# ssb-shield.net
KiCad netlist of a schematic drawn in EAGLE
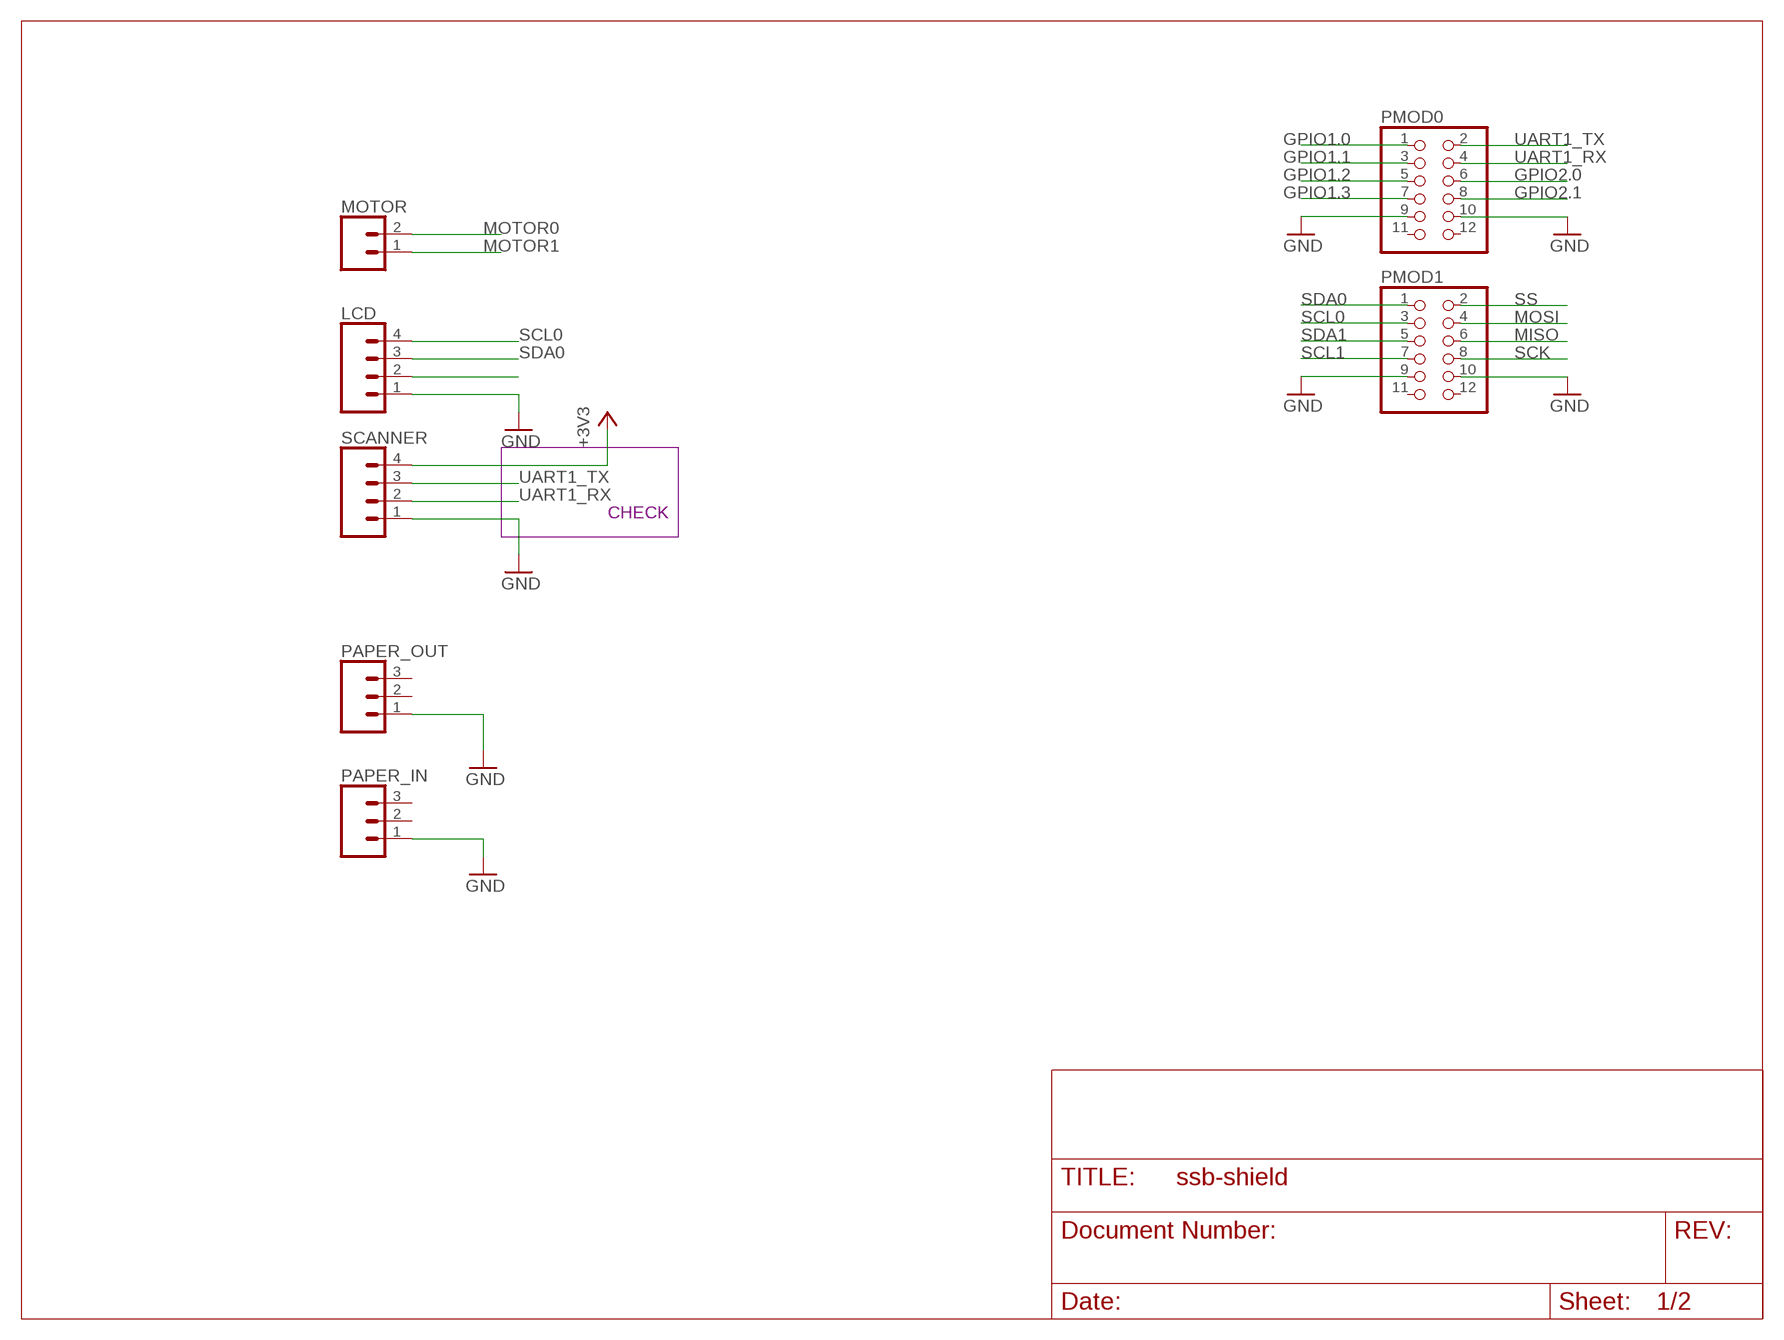
[diagram p0: schematic, sheet 1]
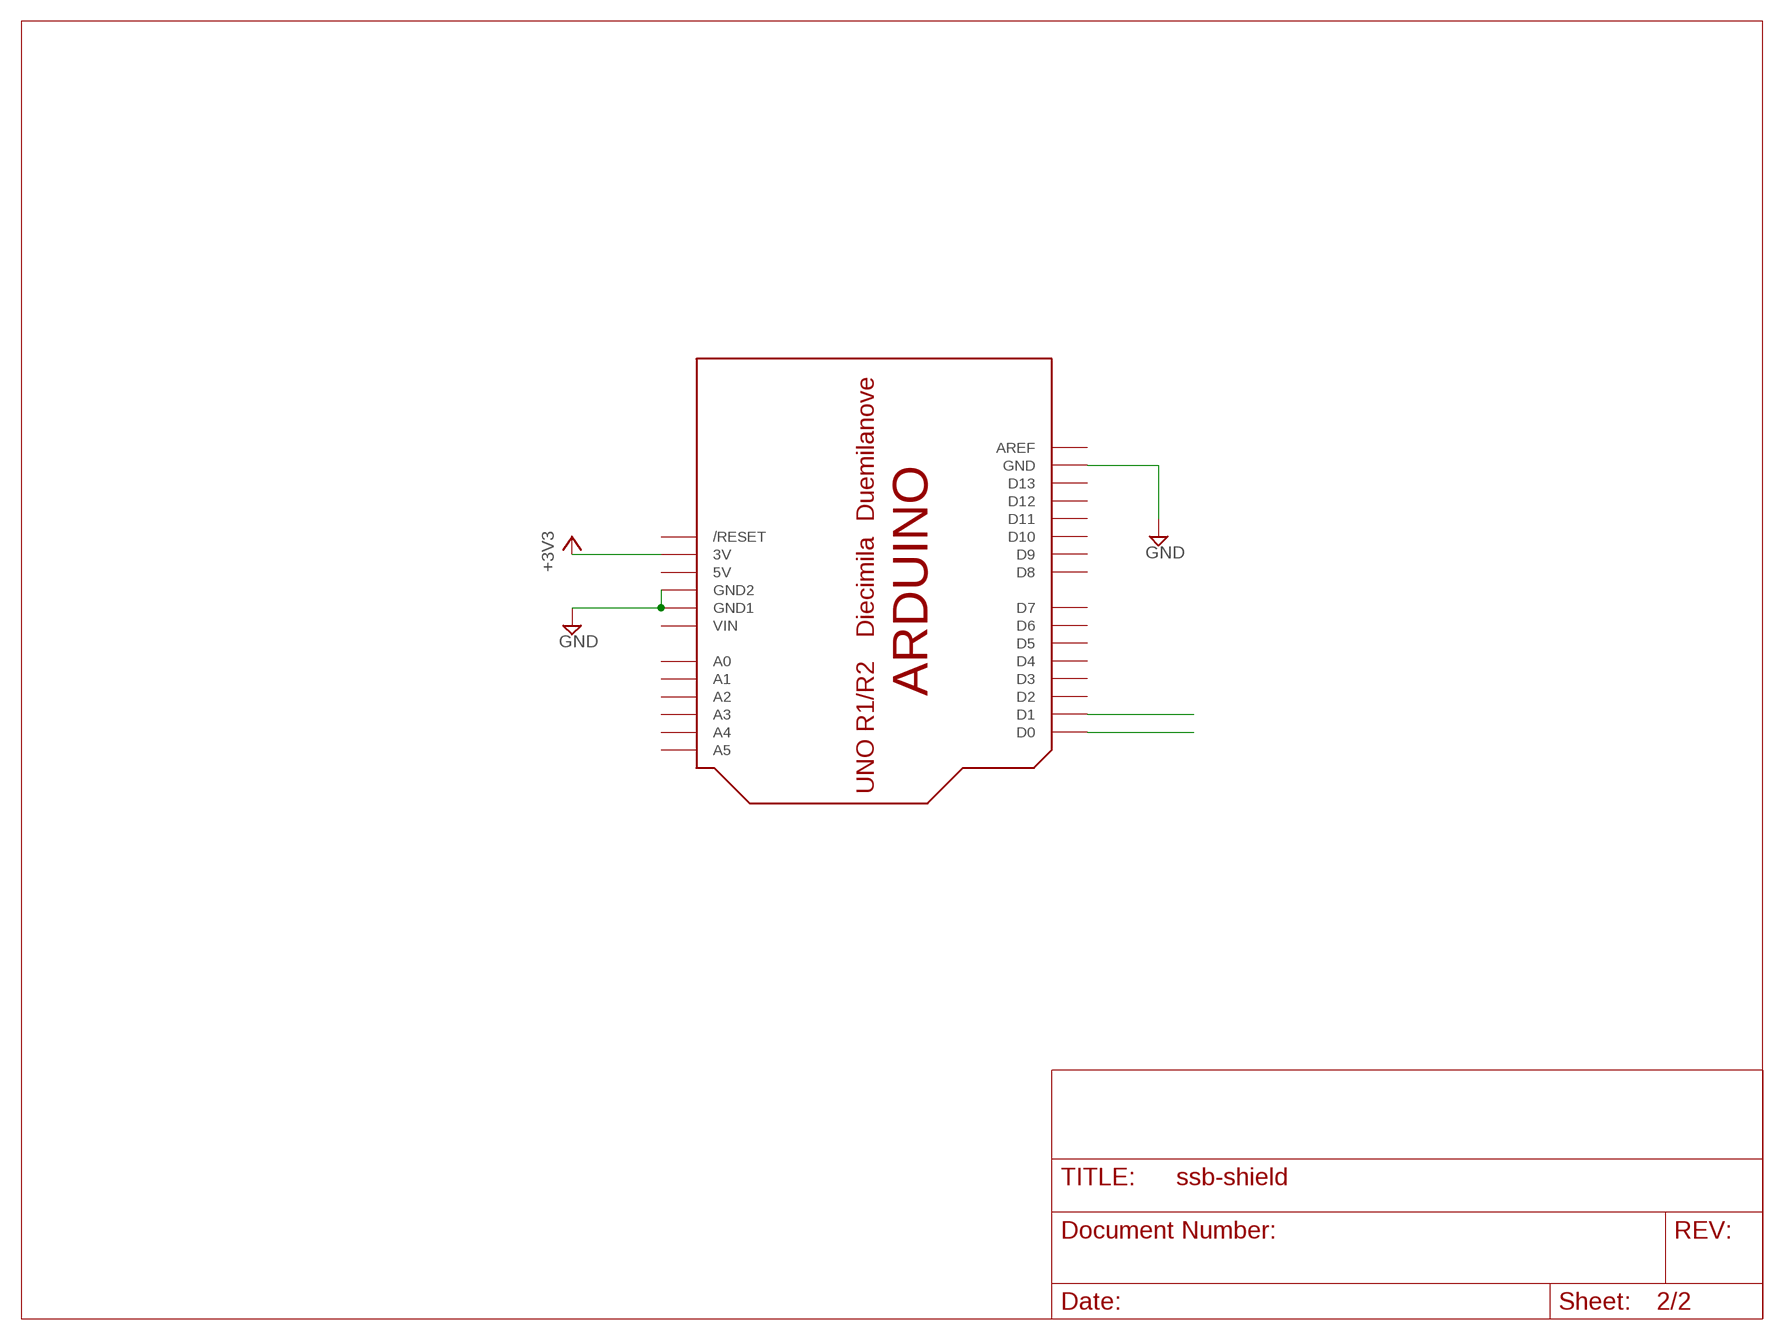
[diagram p1: schematic, sheet 2]

(export (version "E")
  (design (tool "Eeschema 10.0.6"))
  (components
    (comp (ref "LCD")
      (value "CONN_04POLAR_LOCK")
      (footprint "eagle-import:MOLEX-1X4_LOCK")
      (libsource (lib "eagle-import") (part "CONN_04POLAR_LOCK"))
    )
    (comp (ref "MOTOR")
      (value "CONN_02POLAR_LOCK")
      (footprint "eagle-import:MOLEX-1X2_LOCK")
      (libsource (lib "eagle-import") (part "CONN_02POLAR_LOCK"))
    )
    (comp (ref "PAPER_IN")
      (value "CONN_03POLAR_LOCK")
      (footprint "eagle-import:MOLEX-1X3_LOCK")
      (libsource (lib "eagle-import") (part "CONN_03POLAR_LOCK"))
    )
    (comp (ref "PAPER_OUT")
      (value "CONN_03POLAR_LOCK")
      (footprint "eagle-import:MOLEX-1X3_LOCK")
      (libsource (lib "eagle-import") (part "CONN_03POLAR_LOCK"))
    )
    (comp (ref "PMOD0")
      (value "PINHD-2X6")
      (footprint "eagle-import:2X06")
      (libsource (lib "eagle-import") (part "PINHD-2X6"))
    )
    (comp (ref "PMOD1")
      (value "PINHD-2X6")
      (footprint "eagle-import:2X06")
      (libsource (lib "eagle-import") (part "PINHD-2X6"))
    )
    (comp (ref "SCANNER")
      (value "CONN_04POLAR_LOCK")
      (footprint "eagle-import:MOLEX-1X4_LOCK")
      (libsource (lib "eagle-import") (part "CONN_04POLAR_LOCK"))
    )
    (comp (ref "U$2")
      (value "ARDUINO-NOHOLE")
      (footprint "eagle-import:ARDUINO-NOHOLE")
      (libsource (lib "eagle-import") (part "ARDUINO-NOHOLE"))
    )
  )
  (nets
    (net (code "1") (name "+3V3") (class "Default")
      (node (ref "SCANNER") (pin "4") (pinfunction "4_4") (pintype "passive"))
      (node (ref "U$2") (pin "3V") (pinfunction "3V_3V") (pintype "power_in"))
    )
    (net (code "2") (name "5V") (class "Default")
      (node (ref "U$2") (pin "5V") (pinfunction "5V_5V") (pintype "power_in"))
    )
    (net (code "3") (name "GND") (class "Default")
      (node (ref "LCD") (pin "1") (pinfunction "1_1") (pintype "passive"))
      (node (ref "PAPER_IN") (pin "1") (pinfunction "1_1") (pintype "passive"))
      (node (ref "PAPER_OUT") (pin "1") (pinfunction "1_1") (pintype "passive"))
      (node (ref "PMOD0") (pin "10") (pinfunction "10_10") (pintype "passive"))
      (node (ref "PMOD0") (pin "9") (pinfunction "9_9") (pintype "passive"))
      (node (ref "PMOD1") (pin "10") (pinfunction "10_10") (pintype "passive"))
      (node (ref "PMOD1") (pin "9") (pinfunction "9_9") (pintype "passive"))
      (node (ref "SCANNER") (pin "1") (pinfunction "1_1") (pintype "passive"))
      (node (ref "U$2") (pin "GND") (pinfunction "GND_GND") (pintype "power_in"))
      (node (ref "U$2") (pin "GND1") (pinfunction "GND1_GND1") (pintype "power_in"))
      (node (ref "U$2") (pin "GND2") (pinfunction "GND2_GND2") (pintype "power_in"))
    )
    (net (code "4") (name "GPIO1.0") (class "Default")
      (node (ref "PMOD0") (pin "1") (pinfunction "1_1") (pintype "passive"))
    )
    (net (code "5") (name "GPIO1.1") (class "Default")
      (node (ref "PMOD0") (pin "3") (pinfunction "3_3") (pintype "passive"))
    )
    (net (code "6") (name "GPIO1.2") (class "Default")
      (node (ref "PMOD0") (pin "5") (pinfunction "5_5") (pintype "passive"))
    )
    (net (code "7") (name "GPIO1.3") (class "Default")
      (node (ref "PMOD0") (pin "7") (pinfunction "7_7") (pintype "passive"))
    )
    (net (code "8") (name "GPIO2.0") (class "Default")
      (node (ref "PMOD0") (pin "6") (pinfunction "6_6") (pintype "passive"))
    )
    (net (code "9") (name "GPIO2.1") (class "Default")
      (node (ref "PMOD0") (pin "8") (pinfunction "8_8") (pintype "passive"))
    )
    (net (code "10") (name "MISO") (class "Default")
      (node (ref "PMOD1") (pin "6") (pinfunction "6_6") (pintype "passive"))
    )
    (net (code "11") (name "MOSI") (class "Default")
      (node (ref "PMOD1") (pin "4") (pinfunction "4_4") (pintype "passive"))
    )
    (net (code "12") (name "MOTOR0") (class "Default")
      (node (ref "MOTOR") (pin "2") (pinfunction "2_2") (pintype "passive"))
    )
    (net (code "13") (name "MOTOR1") (class "Default")
      (node (ref "MOTOR") (pin "1") (pinfunction "1_1") (pintype "passive"))
    )
    (net (code "14") (name "SCK") (class "Default")
      (node (ref "PMOD1") (pin "8") (pinfunction "8_8") (pintype "passive"))
    )
    (net (code "15") (name "SCL0") (class "Default")
      (node (ref "LCD") (pin "4") (pinfunction "4_4") (pintype "passive"))
      (node (ref "PMOD1") (pin "3") (pinfunction "3_3") (pintype "passive"))
    )
    (net (code "16") (name "SCL1") (class "Default")
      (node (ref "PMOD1") (pin "7") (pinfunction "7_7") (pintype "passive"))
    )
    (net (code "17") (name "SDA0") (class "Default")
      (node (ref "LCD") (pin "3") (pinfunction "3_3") (pintype "passive"))
      (node (ref "PMOD1") (pin "1") (pinfunction "1_1") (pintype "passive"))
    )
    (net (code "18") (name "SDA1") (class "Default")
      (node (ref "PMOD1") (pin "5") (pinfunction "5_5") (pintype "passive"))
    )
    (net (code "19") (name "SS") (class "Default")
      (node (ref "PMOD1") (pin "2") (pinfunction "2_2") (pintype "passive"))
    )
    (net (code "20") (name "UART1_RX") (class "Default")
      (node (ref "PMOD0") (pin "4") (pinfunction "4_4") (pintype "passive"))
      (node (ref "SCANNER") (pin "2") (pinfunction "2_2") (pintype "passive"))
    )
    (net (code "21") (name "UART1_TX") (class "Default")
      (node (ref "PMOD0") (pin "2") (pinfunction "2_2") (pintype "passive"))
      (node (ref "SCANNER") (pin "3") (pinfunction "3_3") (pintype "passive"))
    )
    (net (code "22") (name "VIN") (class "Default")
      (node (ref "U$2") (pin "VIN") (pinfunction "VIN_VIN") (pintype "power_in"))
    )
    (net (code "23") (name "unconnected-(LCD-Pad2)") (class "Default")
      (node (ref "LCD") (pin "2") (pinfunction "2_2") (pintype "passive"))
    )
    (net (code "24") (name "unconnected-(PAPER_IN-Pad2)") (class "Default")
      (node (ref "PAPER_IN") (pin "2") (pinfunction "2_2") (pintype "passive"))
    )
    (net (code "25") (name "unconnected-(PAPER_IN-Pad3)") (class "Default")
      (node (ref "PAPER_IN") (pin "3") (pinfunction "3_3") (pintype "passive"))
    )
    (net (code "26") (name "unconnected-(PAPER_OUT-Pad2)") (class "Default")
      (node (ref "PAPER_OUT") (pin "2") (pinfunction "2_2") (pintype "passive"))
    )
    (net (code "27") (name "unconnected-(PAPER_OUT-Pad3)") (class "Default")
      (node (ref "PAPER_OUT") (pin "3") (pinfunction "3_3") (pintype "passive"))
    )
    (net (code "28") (name "unconnected-(PMOD0-Pad11)") (class "Default")
      (node (ref "PMOD0") (pin "11") (pinfunction "11_11") (pintype "passive"))
    )
    (net (code "29") (name "unconnected-(PMOD0-Pad12)") (class "Default")
      (node (ref "PMOD0") (pin "12") (pinfunction "12_12") (pintype "passive"))
    )
    (net (code "30") (name "unconnected-(PMOD1-Pad11)") (class "Default")
      (node (ref "PMOD1") (pin "11") (pinfunction "11_11") (pintype "passive"))
    )
    (net (code "31") (name "unconnected-(PMOD1-Pad12)") (class "Default")
      (node (ref "PMOD1") (pin "12") (pinfunction "12_12") (pintype "passive"))
    )
    (net (code "32") (name "unconnected-(U$2-PadA0)") (class "Default")
      (node (ref "U$2") (pin "A0") (pinfunction "A0_A0") (pintype "bidirectional"))
    )
    (net (code "33") (name "unconnected-(U$2-PadA1)") (class "Default")
      (node (ref "U$2") (pin "A1") (pinfunction "A1_A1") (pintype "bidirectional"))
    )
    (net (code "34") (name "unconnected-(U$2-PadA2)") (class "Default")
      (node (ref "U$2") (pin "A2") (pinfunction "A2_A2") (pintype "bidirectional"))
    )
    (net (code "35") (name "unconnected-(U$2-PadA3)") (class "Default")
      (node (ref "U$2") (pin "A3") (pinfunction "A3_A3") (pintype "bidirectional"))
    )
    (net (code "36") (name "unconnected-(U$2-PadA4)") (class "Default")
      (node (ref "U$2") (pin "A4") (pinfunction "A4_A4") (pintype "bidirectional"))
    )
    (net (code "37") (name "unconnected-(U$2-PadA5)") (class "Default")
      (node (ref "U$2") (pin "A5") (pinfunction "A5_A5") (pintype "bidirectional"))
    )
    (net (code "38") (name "unconnected-(U$2-PadAREF)") (class "Default")
      (node (ref "U$2") (pin "AREF") (pinfunction "AREF_AREF") (pintype "bidirectional"))
    )
    (net (code "39") (name "unconnected-(U$2-PadD0)") (class "Default")
      (node (ref "U$2") (pin "D0") (pinfunction "D0_D0") (pintype "bidirectional"))
    )
    (net (code "40") (name "unconnected-(U$2-PadD1)") (class "Default")
      (node (ref "U$2") (pin "D1") (pinfunction "D1_D1") (pintype "bidirectional"))
    )
    (net (code "41") (name "unconnected-(U$2-PadD2)") (class "Default")
      (node (ref "U$2") (pin "D2") (pinfunction "D2_D2") (pintype "bidirectional"))
    )
    (net (code "42") (name "unconnected-(U$2-PadD3)") (class "Default")
      (node (ref "U$2") (pin "D3") (pinfunction "D3_D3") (pintype "bidirectional"))
    )
    (net (code "43") (name "unconnected-(U$2-PadD4)") (class "Default")
      (node (ref "U$2") (pin "D4") (pinfunction "D4_D4") (pintype "bidirectional"))
    )
    (net (code "44") (name "unconnected-(U$2-PadD5)") (class "Default")
      (node (ref "U$2") (pin "D5") (pinfunction "D5_D5") (pintype "bidirectional"))
    )
    (net (code "45") (name "unconnected-(U$2-PadD6)") (class "Default")
      (node (ref "U$2") (pin "D6") (pinfunction "D6_D6") (pintype "bidirectional"))
    )
    (net (code "46") (name "unconnected-(U$2-PadD7)") (class "Default")
      (node (ref "U$2") (pin "D7") (pinfunction "D7_D7") (pintype "bidirectional"))
    )
    (net (code "47") (name "unconnected-(U$2-PadD8)") (class "Default")
      (node (ref "U$2") (pin "D8") (pinfunction "D8_D8") (pintype "bidirectional"))
    )
    (net (code "48") (name "unconnected-(U$2-PadD9)") (class "Default")
      (node (ref "U$2") (pin "D9") (pinfunction "D9_D9") (pintype "bidirectional"))
    )
    (net (code "49") (name "unconnected-(U$2-PadD10)") (class "Default")
      (node (ref "U$2") (pin "D10") (pinfunction "D10_D10") (pintype "bidirectional"))
    )
    (net (code "50") (name "unconnected-(U$2-PadD11)") (class "Default")
      (node (ref "U$2") (pin "D11") (pinfunction "D11_D11") (pintype "bidirectional"))
    )
    (net (code "51") (name "unconnected-(U$2-PadD12)") (class "Default")
      (node (ref "U$2") (pin "D12") (pinfunction "D12_D12") (pintype "bidirectional"))
    )
    (net (code "52") (name "unconnected-(U$2-PadD13)") (class "Default")
      (node (ref "U$2") (pin "D13") (pinfunction "D13_D13") (pintype "bidirectional"))
    )
    (net (code "53") (name "unconnected-(U$2-{slash}RESET-PadRESET)") (class "Default")
      (node (ref "U$2") (pin "RESET") (pinfunction "/RESET_RESET") (pintype "bidirectional"))
    )
  )
)
